# Sheet1.net
KiCad netlist of a schematic drawn in Altium Designer
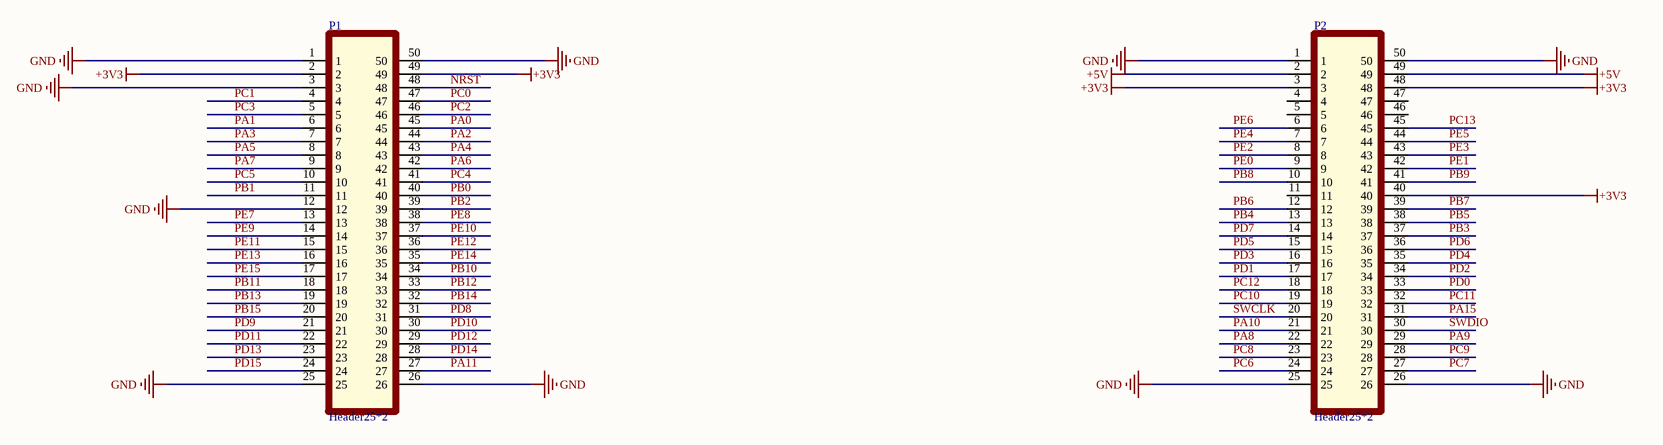
[diagram p0: Sheet1.SchDoc]

(export (version "E")
  (design (tool "Eeschema 10.0.6"))
  (components
    (comp (ref "P1")
      (value "Header25*2")
      (footprint "Pcbheader25doi:hearder25doi")
      (libsource (lib "Schhearder25doi") (part "Header25*2"))
    )
    (comp (ref "P2")
      (value "Header25*2")
      (footprint "Pcbheader25doi:hearder25doi")
      (libsource (lib "Schhearder25doi") (part "Header25*2"))
    )
  )
  (nets
    (net (code "1") (name "+3V3") (class "Default")
      (node (ref "P1") (pin "2") (pinfunction "2_2") (pintype "passive"))
      (node (ref "P1") (pin "49") (pinfunction "49_49") (pintype "passive"))
      (node (ref "P2") (pin "3") (pinfunction "3_3") (pintype "passive"))
      (node (ref "P2") (pin "40") (pinfunction "40_40") (pintype "passive"))
      (node (ref "P2") (pin "48") (pinfunction "48_48") (pintype "passive"))
    )
    (net (code "2") (name "+5V") (class "Default")
      (node (ref "P2") (pin "2") (pinfunction "2_2") (pintype "passive"))
      (node (ref "P2") (pin "49") (pinfunction "49_49") (pintype "passive"))
    )
    (net (code "3") (name "/NRST") (class "Default")
      (node (ref "P1") (pin "48") (pinfunction "48_48") (pintype "passive"))
    )
    (net (code "4") (name "/PA0") (class "Default")
      (node (ref "P1") (pin "45") (pinfunction "45_45") (pintype "passive"))
    )
    (net (code "5") (name "/PA1") (class "Default")
      (node (ref "P1") (pin "6") (pinfunction "6_6") (pintype "passive"))
    )
    (net (code "6") (name "/PA2") (class "Default")
      (node (ref "P1") (pin "44") (pinfunction "44_44") (pintype "passive"))
    )
    (net (code "7") (name "/PA3") (class "Default")
      (node (ref "P1") (pin "7") (pinfunction "7_7") (pintype "passive"))
    )
    (net (code "8") (name "/PA4") (class "Default")
      (node (ref "P1") (pin "43") (pinfunction "43_43") (pintype "passive"))
    )
    (net (code "9") (name "/PA5") (class "Default")
      (node (ref "P1") (pin "8") (pinfunction "8_8") (pintype "passive"))
    )
    (net (code "10") (name "/PA6") (class "Default")
      (node (ref "P1") (pin "42") (pinfunction "42_42") (pintype "passive"))
    )
    (net (code "11") (name "/PA7") (class "Default")
      (node (ref "P1") (pin "9") (pinfunction "9_9") (pintype "passive"))
    )
    (net (code "12") (name "/PA8") (class "Default")
      (node (ref "P2") (pin "22") (pinfunction "22_22") (pintype "passive"))
    )
    (net (code "13") (name "/PA9") (class "Default")
      (node (ref "P2") (pin "29") (pinfunction "29_29") (pintype "passive"))
    )
    (net (code "14") (name "/PA10") (class "Default")
      (node (ref "P2") (pin "21") (pinfunction "21_21") (pintype "passive"))
    )
    (net (code "15") (name "/PA11") (class "Default")
      (node (ref "P1") (pin "27") (pinfunction "27_27") (pintype "passive"))
    )
    (net (code "16") (name "/PA15") (class "Default")
      (node (ref "P2") (pin "31") (pinfunction "31_31") (pintype "passive"))
    )
    (net (code "17") (name "/PB0") (class "Default")
      (node (ref "P1") (pin "40") (pinfunction "40_40") (pintype "passive"))
    )
    (net (code "18") (name "/PB1") (class "Default")
      (node (ref "P1") (pin "11") (pinfunction "11_11") (pintype "passive"))
    )
    (net (code "19") (name "/PB2") (class "Default")
      (node (ref "P1") (pin "39") (pinfunction "39_39") (pintype "passive"))
    )
    (net (code "20") (name "/PB3") (class "Default")
      (node (ref "P2") (pin "37") (pinfunction "37_37") (pintype "passive"))
    )
    (net (code "21") (name "/PB4") (class "Default")
      (node (ref "P2") (pin "13") (pinfunction "13_13") (pintype "passive"))
    )
    (net (code "22") (name "/PB5") (class "Default")
      (node (ref "P2") (pin "38") (pinfunction "38_38") (pintype "passive"))
    )
    (net (code "23") (name "/PB6") (class "Default")
      (node (ref "P2") (pin "12") (pinfunction "12_12") (pintype "passive"))
    )
    (net (code "24") (name "/PB7") (class "Default")
      (node (ref "P2") (pin "39") (pinfunction "39_39") (pintype "passive"))
    )
    (net (code "25") (name "/PB8") (class "Default")
      (node (ref "P2") (pin "10") (pinfunction "10_10") (pintype "passive"))
    )
    (net (code "26") (name "/PB9") (class "Default")
      (node (ref "P2") (pin "41") (pinfunction "41_41") (pintype "passive"))
    )
    (net (code "27") (name "/PB10") (class "Default")
      (node (ref "P1") (pin "34") (pinfunction "34_34") (pintype "passive"))
    )
    (net (code "28") (name "/PB11") (class "Default")
      (node (ref "P1") (pin "18") (pinfunction "18_18") (pintype "passive"))
    )
    (net (code "29") (name "/PB12") (class "Default")
      (node (ref "P1") (pin "33") (pinfunction "33_33") (pintype "passive"))
    )
    (net (code "30") (name "/PB13") (class "Default")
      (node (ref "P1") (pin "19") (pinfunction "19_19") (pintype "passive"))
    )
    (net (code "31") (name "/PB14") (class "Default")
      (node (ref "P1") (pin "32") (pinfunction "32_32") (pintype "passive"))
    )
    (net (code "32") (name "/PB15") (class "Default")
      (node (ref "P1") (pin "20") (pinfunction "20_20") (pintype "passive"))
    )
    (net (code "33") (name "/PC0") (class "Default")
      (node (ref "P1") (pin "47") (pinfunction "47_47") (pintype "passive"))
    )
    (net (code "34") (name "/PC1") (class "Default")
      (node (ref "P1") (pin "4") (pinfunction "4_4") (pintype "passive"))
    )
    (net (code "35") (name "/PC2") (class "Default")
      (node (ref "P1") (pin "46") (pinfunction "46_46") (pintype "passive"))
    )
    (net (code "36") (name "/PC3") (class "Default")
      (node (ref "P1") (pin "5") (pinfunction "5_5") (pintype "passive"))
    )
    (net (code "37") (name "/PC4") (class "Default")
      (node (ref "P1") (pin "41") (pinfunction "41_41") (pintype "passive"))
    )
    (net (code "38") (name "/PC5") (class "Default")
      (node (ref "P1") (pin "10") (pinfunction "10_10") (pintype "passive"))
    )
    (net (code "39") (name "/PC6") (class "Default")
      (node (ref "P2") (pin "24") (pinfunction "24_24") (pintype "passive"))
    )
    (net (code "40") (name "/PC7") (class "Default")
      (node (ref "P2") (pin "27") (pinfunction "27_27") (pintype "passive"))
    )
    (net (code "41") (name "/PC8") (class "Default")
      (node (ref "P2") (pin "23") (pinfunction "23_23") (pintype "passive"))
    )
    (net (code "42") (name "/PC9") (class "Default")
      (node (ref "P2") (pin "28") (pinfunction "28_28") (pintype "passive"))
    )
    (net (code "43") (name "/PC10") (class "Default")
      (node (ref "P2") (pin "19") (pinfunction "19_19") (pintype "passive"))
    )
    (net (code "44") (name "/PC11") (class "Default")
      (node (ref "P2") (pin "32") (pinfunction "32_32") (pintype "passive"))
    )
    (net (code "45") (name "/PC12") (class "Default")
      (node (ref "P2") (pin "18") (pinfunction "18_18") (pintype "passive"))
    )
    (net (code "46") (name "/PC13") (class "Default")
      (node (ref "P2") (pin "45") (pinfunction "45_45") (pintype "passive"))
    )
    (net (code "47") (name "/PD0") (class "Default")
      (node (ref "P2") (pin "33") (pinfunction "33_33") (pintype "passive"))
    )
    (net (code "48") (name "/PD1") (class "Default")
      (node (ref "P2") (pin "17") (pinfunction "17_17") (pintype "passive"))
    )
    (net (code "49") (name "/PD2") (class "Default")
      (node (ref "P2") (pin "34") (pinfunction "34_34") (pintype "passive"))
    )
    (net (code "50") (name "/PD3") (class "Default")
      (node (ref "P2") (pin "16") (pinfunction "16_16") (pintype "passive"))
    )
    (net (code "51") (name "/PD4") (class "Default")
      (node (ref "P2") (pin "35") (pinfunction "35_35") (pintype "passive"))
    )
    (net (code "52") (name "/PD5") (class "Default")
      (node (ref "P2") (pin "15") (pinfunction "15_15") (pintype "passive"))
    )
    (net (code "53") (name "/PD6") (class "Default")
      (node (ref "P2") (pin "36") (pinfunction "36_36") (pintype "passive"))
    )
    (net (code "54") (name "/PD7") (class "Default")
      (node (ref "P2") (pin "14") (pinfunction "14_14") (pintype "passive"))
    )
    (net (code "55") (name "/PD8") (class "Default")
      (node (ref "P1") (pin "31") (pinfunction "31_31") (pintype "passive"))
    )
    (net (code "56") (name "/PD9") (class "Default")
      (node (ref "P1") (pin "21") (pinfunction "21_21") (pintype "passive"))
    )
    (net (code "57") (name "/PD10") (class "Default")
      (node (ref "P1") (pin "30") (pinfunction "30_30") (pintype "passive"))
    )
    (net (code "58") (name "/PD11") (class "Default")
      (node (ref "P1") (pin "22") (pinfunction "22_22") (pintype "passive"))
    )
    (net (code "59") (name "/PD12") (class "Default")
      (node (ref "P1") (pin "29") (pinfunction "29_29") (pintype "passive"))
    )
    (net (code "60") (name "/PD13") (class "Default")
      (node (ref "P1") (pin "23") (pinfunction "23_23") (pintype "passive"))
    )
    (net (code "61") (name "/PD14") (class "Default")
      (node (ref "P1") (pin "28") (pinfunction "28_28") (pintype "passive"))
    )
    (net (code "62") (name "/PD15") (class "Default")
      (node (ref "P1") (pin "24") (pinfunction "24_24") (pintype "passive"))
    )
    (net (code "63") (name "/PE0") (class "Default")
      (node (ref "P2") (pin "9") (pinfunction "9_9") (pintype "passive"))
    )
    (net (code "64") (name "/PE1") (class "Default")
      (node (ref "P2") (pin "42") (pinfunction "42_42") (pintype "passive"))
    )
    (net (code "65") (name "/PE2") (class "Default")
      (node (ref "P2") (pin "8") (pinfunction "8_8") (pintype "passive"))
    )
    (net (code "66") (name "/PE3") (class "Default")
      (node (ref "P2") (pin "43") (pinfunction "43_43") (pintype "passive"))
    )
    (net (code "67") (name "/PE4") (class "Default")
      (node (ref "P2") (pin "7") (pinfunction "7_7") (pintype "passive"))
    )
    (net (code "68") (name "/PE5") (class "Default")
      (node (ref "P2") (pin "44") (pinfunction "44_44") (pintype "passive"))
    )
    (net (code "69") (name "/PE6") (class "Default")
      (node (ref "P2") (pin "6") (pinfunction "6_6") (pintype "passive"))
    )
    (net (code "70") (name "/PE7") (class "Default")
      (node (ref "P1") (pin "13") (pinfunction "13_13") (pintype "passive"))
    )
    (net (code "71") (name "/PE8") (class "Default")
      (node (ref "P1") (pin "38") (pinfunction "38_38") (pintype "passive"))
    )
    (net (code "72") (name "/PE9") (class "Default")
      (node (ref "P1") (pin "14") (pinfunction "14_14") (pintype "passive"))
    )
    (net (code "73") (name "/PE10") (class "Default")
      (node (ref "P1") (pin "37") (pinfunction "37_37") (pintype "passive"))
    )
    (net (code "74") (name "/PE11") (class "Default")
      (node (ref "P1") (pin "15") (pinfunction "15_15") (pintype "passive"))
    )
    (net (code "75") (name "/PE12") (class "Default")
      (node (ref "P1") (pin "36") (pinfunction "36_36") (pintype "passive"))
    )
    (net (code "76") (name "/PE13") (class "Default")
      (node (ref "P1") (pin "16") (pinfunction "16_16") (pintype "passive"))
    )
    (net (code "77") (name "/PE14") (class "Default")
      (node (ref "P1") (pin "35") (pinfunction "35_35") (pintype "passive"))
    )
    (net (code "78") (name "/PE15") (class "Default")
      (node (ref "P1") (pin "17") (pinfunction "17_17") (pintype "passive"))
    )
    (net (code "79") (name "/SWCLK") (class "Default")
      (node (ref "P2") (pin "20") (pinfunction "20_20") (pintype "passive"))
    )
    (net (code "80") (name "/SWDIO") (class "Default")
      (node (ref "P2") (pin "30") (pinfunction "30_30") (pintype "passive"))
    )
    (net (code "81") (name "GND") (class "Default")
      (node (ref "P1") (pin "1") (pinfunction "1_1") (pintype "passive"))
      (node (ref "P1") (pin "12") (pinfunction "12_12") (pintype "passive"))
      (node (ref "P1") (pin "25") (pinfunction "25_25") (pintype "passive"))
      (node (ref "P1") (pin "26") (pinfunction "26_26") (pintype "passive"))
      (node (ref "P1") (pin "3") (pinfunction "3_3") (pintype "passive"))
      (node (ref "P1") (pin "50") (pinfunction "50_50") (pintype "passive"))
      (node (ref "P2") (pin "1") (pinfunction "1_1") (pintype "passive"))
      (node (ref "P2") (pin "25") (pinfunction "25_25") (pintype "passive"))
      (node (ref "P2") (pin "26") (pinfunction "26_26") (pintype "passive"))
      (node (ref "P2") (pin "50") (pinfunction "50_50") (pintype "passive"))
    )
    (net (code "82") (name "unconnected-(P2-Pad4)") (class "Default")
      (node (ref "P2") (pin "4") (pinfunction "4_4") (pintype "passive"))
    )
    (net (code "83") (name "unconnected-(P2-Pad5)") (class "Default")
      (node (ref "P2") (pin "5") (pinfunction "5_5") (pintype "passive"))
    )
    (net (code "84") (name "unconnected-(P2-Pad11)") (class "Default")
      (node (ref "P2") (pin "11") (pinfunction "11_11") (pintype "passive"))
    )
    (net (code "85") (name "unconnected-(P2-Pad46)") (class "Default")
      (node (ref "P2") (pin "46") (pinfunction "46_46") (pintype "passive"))
    )
    (net (code "86") (name "unconnected-(P2-Pad47)") (class "Default")
      (node (ref "P2") (pin "47") (pinfunction "47_47") (pintype "passive"))
    )
  )
)
